# Group6_ADC1.net
KiCad netlist of a schematic drawn in EAGLE
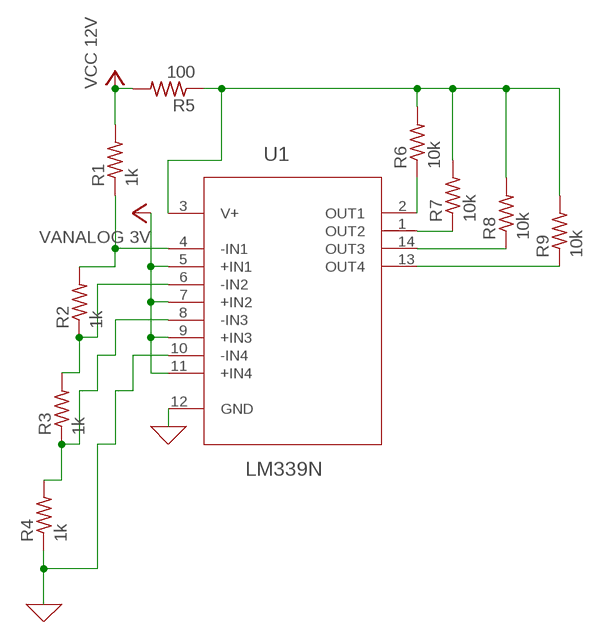
[diagram p0: schematic, sheet 1]

(export (version "E")
  (design (tool "Eeschema 10.0.6"))
  (components
    (comp (ref "R1")
      (value "1k")
      (footprint "eagle-import:0204_7")
      (libsource (lib "eagle-import") (part "R-US_0204/7"))
    )
    (comp (ref "R2")
      (value "1k")
      (footprint "eagle-import:0204_7")
      (libsource (lib "eagle-import") (part "R-US_0204/7"))
    )
    (comp (ref "R3")
      (value "1k")
      (footprint "eagle-import:0204_7")
      (libsource (lib "eagle-import") (part "R-US_0204/7"))
    )
    (comp (ref "R4")
      (value "1k")
      (footprint "eagle-import:0204_7")
      (libsource (lib "eagle-import") (part "R-US_0204/7"))
    )
    (comp (ref "R5")
      (value "100")
      (footprint "eagle-import:0204_7")
      (libsource (lib "eagle-import") (part "R-US_0204/7"))
    )
    (comp (ref "R6")
      (value "10k")
      (footprint "eagle-import:0204_7")
      (libsource (lib "eagle-import") (part "R-US_0204/7"))
    )
    (comp (ref "R7")
      (value "10k")
      (footprint "eagle-import:0204_7")
      (libsource (lib "eagle-import") (part "R-US_0204/7"))
    )
    (comp (ref "R8")
      (value "10k")
      (footprint "eagle-import:0204_7")
      (libsource (lib "eagle-import") (part "R-US_0204/7"))
    )
    (comp (ref "R9")
      (value "10k")
      (footprint "eagle-import:0204_7")
      (libsource (lib "eagle-import") (part "R-US_0204/7"))
    )
    (comp (ref "U1")
      (value "LM339N")
      (footprint "eagle-import:DIP254P762X508-14")
      (fields (field (name "MF") "ON Semiconductor"))
      (libsource (lib "eagle-import") (part "LM339N"))
    )
  )
  (nets
    (net (code "1") (name "GND") (class "Default")
      (node (ref "R4") (pin "1") (pinfunction "1_1") (pintype "passive"))
      (node (ref "U1") (pin "10") (pinfunction "-IN4_10") (pintype "input"))
      (node (ref "U1") (pin "12") (pinfunction "GND_12") (pintype "passive"))
    )
    (net (code "2") (name "Net-(U1--IN1)") (class "Default")
      (node (ref "R1") (pin "1") (pinfunction "1_1") (pintype "passive"))
      (node (ref "R2") (pin "2") (pinfunction "2_2") (pintype "passive"))
      (node (ref "U1") (pin "4") (pinfunction "-IN1_4") (pintype "input"))
    )
    (net (code "3") (name "Net-(U1--IN2)") (class "Default")
      (node (ref "R2") (pin "1") (pinfunction "1_1") (pintype "passive"))
      (node (ref "R3") (pin "2") (pinfunction "2_2") (pintype "passive"))
      (node (ref "U1") (pin "6") (pinfunction "-IN2_6") (pintype "input"))
    )
    (net (code "4") (name "Net-(U1--IN3)") (class "Default")
      (node (ref "R3") (pin "1") (pinfunction "1_1") (pintype "passive"))
      (node (ref "R4") (pin "2") (pinfunction "2_2") (pintype "passive"))
      (node (ref "U1") (pin "8") (pinfunction "-IN3_8") (pintype "input"))
    )
    (net (code "5") (name "Net-(U1-OUT1)") (class "Default")
      (node (ref "R6") (pin "1") (pinfunction "1_1") (pintype "passive"))
      (node (ref "U1") (pin "2") (pinfunction "OUT1_2") (pintype "output"))
    )
    (net (code "6") (name "Net-(U1-OUT2)") (class "Default")
      (node (ref "R7") (pin "1") (pinfunction "1_1") (pintype "passive"))
      (node (ref "U1") (pin "1") (pinfunction "OUT2_1") (pintype "output"))
    )
    (net (code "7") (name "Net-(U1-OUT3)") (class "Default")
      (node (ref "R8") (pin "1") (pinfunction "1_1") (pintype "passive"))
      (node (ref "U1") (pin "14") (pinfunction "OUT3_14") (pintype "output"))
    )
    (net (code "8") (name "Net-(U1-OUT4)") (class "Default")
      (node (ref "R9") (pin "1") (pinfunction "1_1") (pintype "passive"))
      (node (ref "U1") (pin "13") (pinfunction "OUT4_13") (pintype "output"))
    )
    (net (code "9") (name "Net-(U1-V+)") (class "Default")
      (node (ref "R5") (pin "1") (pinfunction "1_1") (pintype "passive"))
      (node (ref "R6") (pin "2") (pinfunction "2_2") (pintype "passive"))
      (node (ref "R7") (pin "2") (pinfunction "2_2") (pintype "passive"))
      (node (ref "R8") (pin "2") (pinfunction "2_2") (pintype "passive"))
      (node (ref "R9") (pin "2") (pinfunction "2_2") (pintype "passive"))
      (node (ref "U1") (pin "3") (pinfunction "V+_3") (pintype "power_in"))
    )
    (net (code "10") (name "VANALOG 3V") (class "Default")
      (node (ref "R1") (pin "2") (pinfunction "2_2") (pintype "passive"))
      (node (ref "R5") (pin "2") (pinfunction "2_2") (pintype "passive"))
      (node (ref "U1") (pin "11") (pinfunction "+IN4_11") (pintype "input"))
      (node (ref "U1") (pin "5") (pinfunction "+IN1_5") (pintype "input"))
      (node (ref "U1") (pin "7") (pinfunction "+IN2_7") (pintype "input"))
      (node (ref "U1") (pin "9") (pinfunction "+IN3_9") (pintype "input"))
    )
  )
)
